# Button_Led_Buzzer.net
KiCad netlist of a schematic drawn in EAGLE
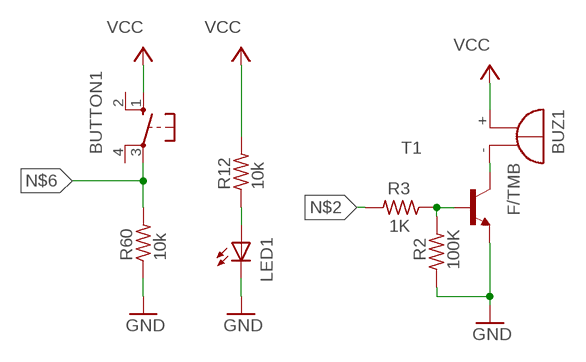
[diagram p0: schematic, sheet 1]

(export (version "E")
  (design (tool "Eeschema 10.0.6"))
  (components
    (comp (ref "BUTTON1")
      (value "10-XX")
      (footprint "eagle-import:B3F-10XX")
      (fields (field (name "MPN") "B3F-1000"))
      (libsource (lib "eagle-import") (part "10-XX"))
    )
    (comp (ref "BUZ1")
      (value "F/TMB")
      (footprint "eagle-import:F_TMB")
      (libsource (lib "eagle-import") (part "F/TMB"))
    )
    (comp (ref "LED1")
      (value "LED3MM")
      (footprint "eagle-import:LED3MM")
      (libsource (lib "eagle-import") (part "LED3MM"))
    )
    (comp (ref "R2")
      (value "100K")
      (footprint "eagle-import:0204_7")
      (libsource (lib "eagle-import") (part "R-US_0204/7"))
    )
    (comp (ref "R3")
      (value "1K")
      (footprint "eagle-import:0204_7")
      (libsource (lib "eagle-import") (part "R-US_0204/7"))
    )
    (comp (ref "R12")
      (value "10k")
      (footprint "eagle-import:0204_7")
      (libsource (lib "eagle-import") (part "R-US_0204/7"))
    )
    (comp (ref "R60")
      (value "10k")
      (footprint "eagle-import:0204_7")
      (libsource (lib "eagle-import") (part "R-US_0204/7"))
    )
    (comp (ref "T1")
      (value "BC547-NPN-TO92-CBE")
      (footprint "eagle-import:TO92-CBE")
      (libsource (lib "eagle-import") (part "-NPN-TO92-CBEBC547"))
    )
  )
  (nets
    (net (code "1") (name "GND") (class "Default")
      (node (ref "LED1") (pin "K") (pinfunction "C_K") (pintype "passive"))
      (node (ref "R2") (pin "1") (pinfunction "1_1") (pintype "passive"))
      (node (ref "R60") (pin "1") (pinfunction "1_1") (pintype "passive"))
      (node (ref "T1") (pin "E") (pinfunction "E_E") (pintype "passive"))
    )
    (net (code "2") (name "N$2") (class "Default")
      (node (ref "R3") (pin "2") (pinfunction "2_2") (pintype "passive"))
    )
    (net (code "3") (name "N$6") (class "Default")
      (node (ref "BUTTON1") (pin "3") (pinfunction "P_3") (pintype "passive"))
      (node (ref "R60") (pin "2") (pinfunction "2_2") (pintype "passive"))
    )
    (net (code "4") (name "Net-(BUZ1-Pad-)") (class "Default")
      (node (ref "BUZ1") (pin "-") (pinfunction "-_-") (pintype "passive"))
      (node (ref "T1") (pin "C") (pinfunction "C_C") (pintype "passive"))
    )
    (net (code "5") (name "Net-(LED1-PadA)") (class "Default")
      (node (ref "LED1") (pin "A") (pinfunction "A_A") (pintype "passive"))
      (node (ref "R12") (pin "1") (pinfunction "1_1") (pintype "passive"))
    )
    (net (code "6") (name "Net-(R2-Pad2)") (class "Default")
      (node (ref "R2") (pin "2") (pinfunction "2_2") (pintype "passive"))
      (node (ref "R3") (pin "1") (pinfunction "1_1") (pintype "passive"))
      (node (ref "T1") (pin "B") (pinfunction "B_B") (pintype "passive"))
    )
    (net (code "7") (name "VCC") (class "Default")
      (node (ref "BUTTON1") (pin "1") (pinfunction "S_1") (pintype "passive"))
      (node (ref "BUZ1") (pin "+") (pinfunction "+_+") (pintype "passive"))
      (node (ref "R12") (pin "2") (pinfunction "2_2") (pintype "passive"))
    )
    (net (code "8") (name "unconnected-(BUTTON1-P1-Pad4)") (class "Default")
      (node (ref "BUTTON1") (pin "4") (pinfunction "P1_4") (pintype "passive"))
    )
    (net (code "9") (name "unconnected-(BUTTON1-S1-Pad2)") (class "Default")
      (node (ref "BUTTON1") (pin "2") (pinfunction "S1_2") (pintype "passive"))
    )
  )
)
